# wiring1.net
KiCad netlist of a schematic drawn in EAGLE
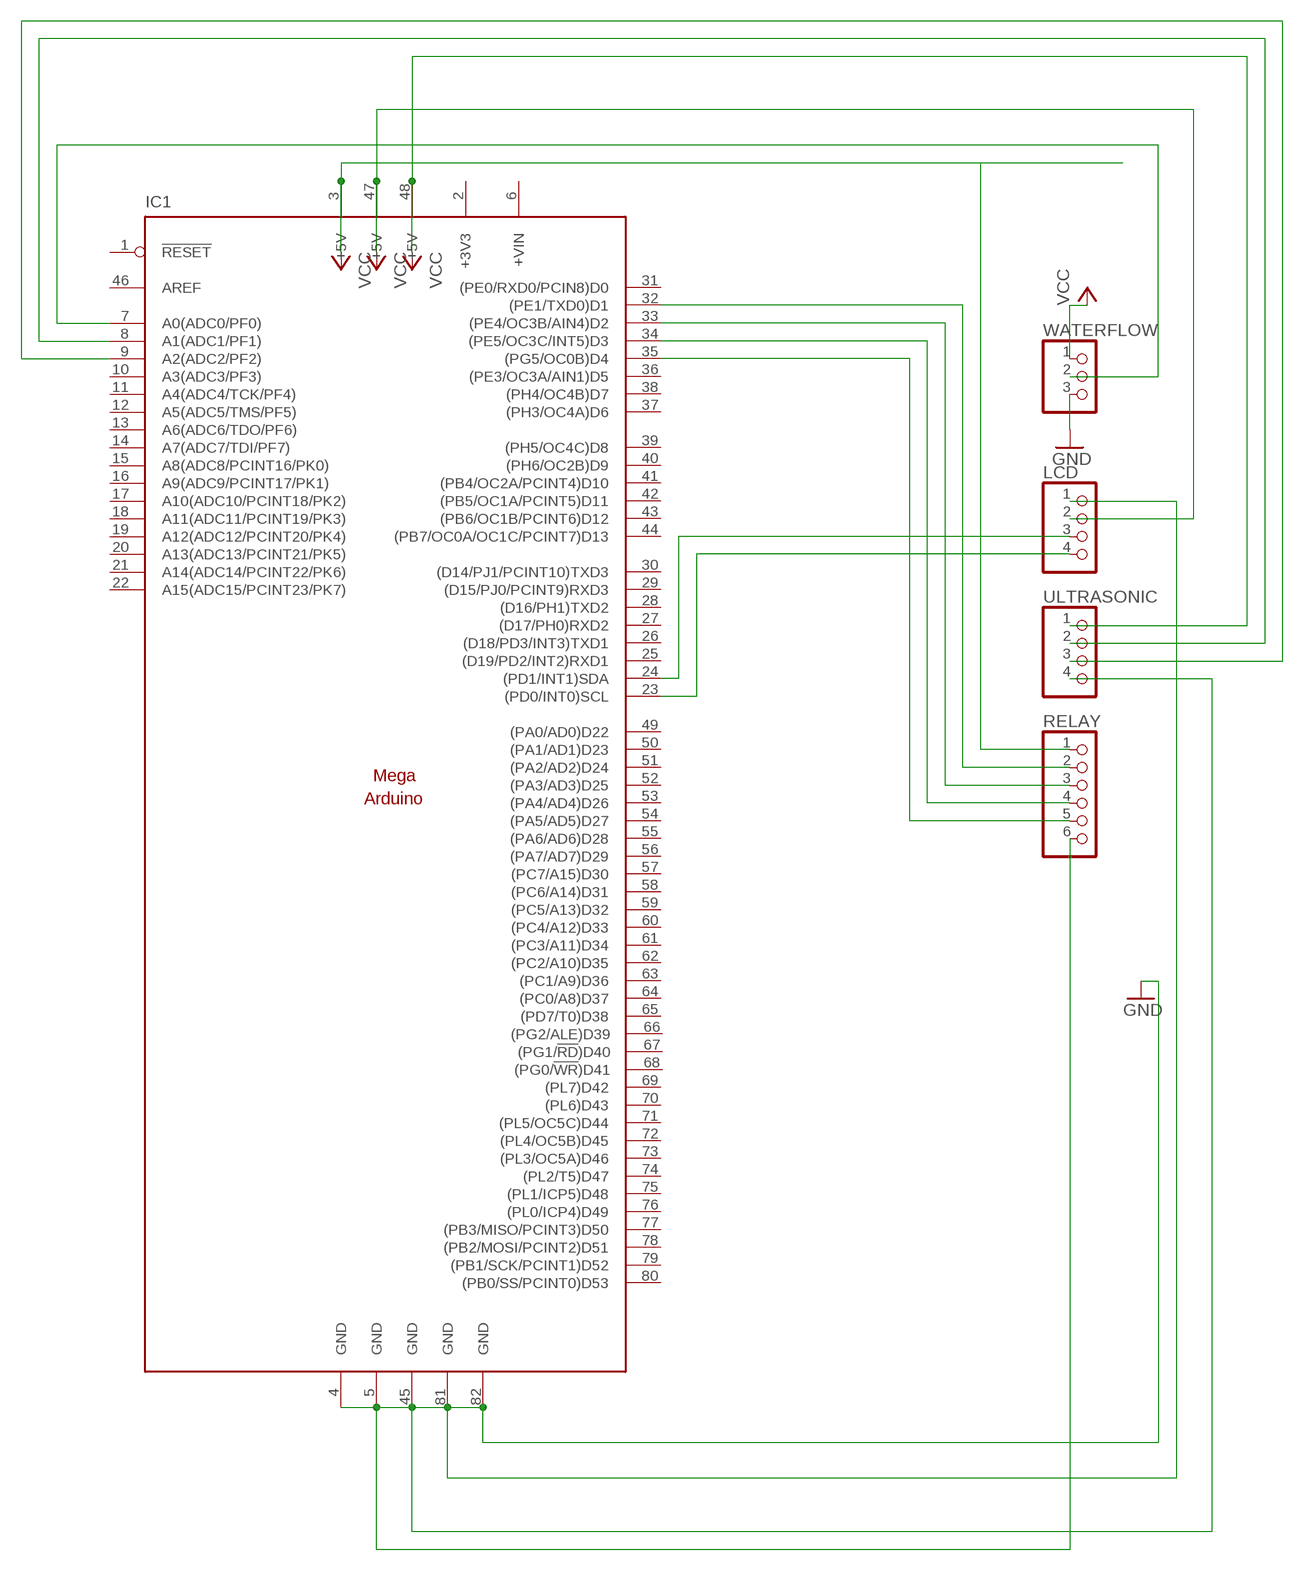
[diagram p0: schematic, sheet 1]

(export (version "E")
  (design (tool "Eeschema 10.0.6"))
  (components
    (comp (ref "IC1")
      (value "ARDUINOMEGA")
      (footprint "eagle-import:ARDUINOMEGA")
      (libsource (lib "eagle-import") (part "ARDUINOMEGA"))
    )
    (comp (ref "LCD")
      (value "PINHD-1X4")
      (footprint "eagle-import:1X04")
      (libsource (lib "eagle-import") (part "PINHD-1X4"))
    )
    (comp (ref "RELAY")
      (value "PINHD-1X6")
      (footprint "eagle-import:1X06")
      (libsource (lib "eagle-import") (part "PINHD-1X6"))
    )
    (comp (ref "ULTRASONIC")
      (value "PINHD-1X4")
      (footprint "eagle-import:1X04")
      (libsource (lib "eagle-import") (part "PINHD-1X4"))
    )
    (comp (ref "WATERFLOW")
      (value "PINHD-1X3")
      (footprint "eagle-import:1X03")
      (libsource (lib "eagle-import") (part "PINHD-1X3"))
    )
  )
  (nets
    (net (code "1") (name "/+3V3") (class "Default")
      (node (ref "IC1") (pin "2") (pinfunction "+3V3_2") (pintype "power_in"))
    )
    (net (code "2") (name "/+VIN") (class "Default")
      (node (ref "IC1") (pin "6") (pinfunction "+VIN_6") (pintype "power_in"))
    )
    (net (code "3") (name "GND") (class "Default")
      (node (ref "IC1") (pin "4") (pinfunction "GND_4") (pintype "power_in"))
      (node (ref "IC1") (pin "45") (pinfunction "GND_45") (pintype "power_in"))
      (node (ref "IC1") (pin "5") (pinfunction "GND_5") (pintype "power_in"))
      (node (ref "IC1") (pin "81") (pinfunction "GND_81") (pintype "power_in"))
      (node (ref "IC1") (pin "82") (pinfunction "GND_82") (pintype "power_in"))
      (node (ref "LCD") (pin "1") (pinfunction "1_1") (pintype "passive"))
      (node (ref "RELAY") (pin "6") (pinfunction "6_6") (pintype "passive"))
      (node (ref "ULTRASONIC") (pin "4") (pinfunction "4_4") (pintype "passive"))
      (node (ref "WATERFLOW") (pin "3") (pinfunction "3_3") (pintype "passive"))
    )
    (net (code "4") (name "Net-(IC1-(PD0{slash}INT0)SCL)") (class "Default")
      (node (ref "IC1") (pin "23") (pinfunction "(PD0/INT0)SCL_23") (pintype "bidirectional"))
      (node (ref "LCD") (pin "4") (pinfunction "4_4") (pintype "passive"))
    )
    (net (code "5") (name "Net-(IC1-(PD1{slash}INT1)SDA)") (class "Default")
      (node (ref "IC1") (pin "24") (pinfunction "(PD1/INT1)SDA_24") (pintype "bidirectional"))
      (node (ref "LCD") (pin "3") (pinfunction "3_3") (pintype "passive"))
    )
    (net (code "6") (name "Net-(IC1-(PE1{slash}TXD0)D1)") (class "Default")
      (node (ref "IC1") (pin "32") (pinfunction "(PE1/TXD0)D1_32") (pintype "bidirectional"))
      (node (ref "RELAY") (pin "2") (pinfunction "2_2") (pintype "passive"))
    )
    (net (code "7") (name "Net-(IC1-(PE4{slash}OC3B{slash}AIN4)D2)") (class "Default")
      (node (ref "IC1") (pin "33") (pinfunction "(PE4/OC3B/AIN4)D2_33") (pintype "bidirectional"))
      (node (ref "RELAY") (pin "3") (pinfunction "3_3") (pintype "passive"))
    )
    (net (code "8") (name "Net-(IC1-(PE5{slash}OC3C{slash}INT5)D3)") (class "Default")
      (node (ref "IC1") (pin "34") (pinfunction "(PE5/OC3C/INT5)D3_34") (pintype "bidirectional"))
      (node (ref "RELAY") (pin "4") (pinfunction "4_4") (pintype "passive"))
    )
    (net (code "9") (name "Net-(IC1-(PG5{slash}OC0B)D4)") (class "Default")
      (node (ref "IC1") (pin "35") (pinfunction "(PG5/OC0B)D4_35") (pintype "bidirectional"))
      (node (ref "RELAY") (pin "5") (pinfunction "5_5") (pintype "passive"))
    )
    (net (code "10") (name "Net-(IC1-A0(ADC0{slash}PF0))") (class "Default")
      (node (ref "IC1") (pin "7") (pinfunction "A0(ADC0/PF0)_7") (pintype "bidirectional"))
      (node (ref "WATERFLOW") (pin "2") (pinfunction "2_2") (pintype "passive"))
    )
    (net (code "11") (name "Net-(IC1-A1(ADC1{slash}PF1))") (class "Default")
      (node (ref "IC1") (pin "8") (pinfunction "A1(ADC1/PF1)_8") (pintype "bidirectional"))
      (node (ref "ULTRASONIC") (pin "2") (pinfunction "2_2") (pintype "passive"))
    )
    (net (code "12") (name "Net-(IC1-A2(ADC2{slash}PF2))") (class "Default")
      (node (ref "IC1") (pin "9") (pinfunction "A2(ADC2/PF2)_9") (pintype "bidirectional"))
      (node (ref "ULTRASONIC") (pin "3") (pinfunction "3_3") (pintype "passive"))
    )
    (net (code "13") (name "VCC") (class "Default")
      (node (ref "IC1") (pin "3") (pinfunction "+5V_3") (pintype "power_in"))
      (node (ref "IC1") (pin "47") (pinfunction "+5V_47") (pintype "power_in"))
      (node (ref "IC1") (pin "48") (pinfunction "+5V_48") (pintype "power_in"))
      (node (ref "LCD") (pin "2") (pinfunction "2_2") (pintype "passive"))
      (node (ref "RELAY") (pin "1") (pinfunction "1_1") (pintype "passive"))
      (node (ref "ULTRASONIC") (pin "1") (pinfunction "1_1") (pintype "passive"))
      (node (ref "WATERFLOW") (pin "1") (pinfunction "1_1") (pintype "passive"))
    )
    (net (code "14") (name "unconnected-(IC1-(D14{slash}PJ1{slash}PCINT10)TXD3-Pad30)") (class "Default")
      (node (ref "IC1") (pin "30") (pinfunction "(D14/PJ1/PCINT10)TXD3_30") (pintype "bidirectional"))
    )
    (net (code "15") (name "unconnected-(IC1-(D15{slash}PJ0{slash}PCINT9)RXD3-Pad29)") (class "Default")
      (node (ref "IC1") (pin "29") (pinfunction "(D15/PJ0/PCINT9)RXD3_29") (pintype "bidirectional"))
    )
    (net (code "16") (name "unconnected-(IC1-(D16{slash}PH1)TXD2-Pad28)") (class "Default")
      (node (ref "IC1") (pin "28") (pinfunction "(D16/PH1)TXD2_28") (pintype "bidirectional"))
    )
    (net (code "17") (name "unconnected-(IC1-(D17{slash}PH0)RXD2-Pad27)") (class "Default")
      (node (ref "IC1") (pin "27") (pinfunction "(D17/PH0)RXD2_27") (pintype "bidirectional"))
    )
    (net (code "18") (name "unconnected-(IC1-(D18{slash}PD3{slash}INT3)TXD1-Pad26)") (class "Default")
      (node (ref "IC1") (pin "26") (pinfunction "(D18/PD3/INT3)TXD1_26") (pintype "bidirectional"))
    )
    (net (code "19") (name "unconnected-(IC1-(D19{slash}PD2{slash}INT2)RXD1-Pad25)") (class "Default")
      (node (ref "IC1") (pin "25") (pinfunction "(D19/PD2/INT2)RXD1_25") (pintype "bidirectional"))
    )
    (net (code "20") (name "unconnected-(IC1-(PA0{slash}AD0)D22-Pad49)") (class "Default")
      (node (ref "IC1") (pin "49") (pinfunction "(PA0/AD0)D22_49") (pintype "bidirectional"))
    )
    (net (code "21") (name "unconnected-(IC1-(PA1{slash}AD1)D23-Pad50)") (class "Default")
      (node (ref "IC1") (pin "50") (pinfunction "(PA1/AD1)D23_50") (pintype "bidirectional"))
    )
    (net (code "22") (name "unconnected-(IC1-(PA2{slash}AD2)D24-Pad51)") (class "Default")
      (node (ref "IC1") (pin "51") (pinfunction "(PA2/AD2)D24_51") (pintype "bidirectional"))
    )
    (net (code "23") (name "unconnected-(IC1-(PA3{slash}AD3)D25-Pad52)") (class "Default")
      (node (ref "IC1") (pin "52") (pinfunction "(PA3/AD3)D25_52") (pintype "bidirectional"))
    )
    (net (code "24") (name "unconnected-(IC1-(PA4{slash}AD4)D26-Pad53)") (class "Default")
      (node (ref "IC1") (pin "53") (pinfunction "(PA4/AD4)D26_53") (pintype "bidirectional"))
    )
    (net (code "25") (name "unconnected-(IC1-(PA5{slash}AD5)D27-Pad54)") (class "Default")
      (node (ref "IC1") (pin "54") (pinfunction "(PA5/AD5)D27_54") (pintype "bidirectional"))
    )
    (net (code "26") (name "unconnected-(IC1-(PA6{slash}AD6)D28-Pad55)") (class "Default")
      (node (ref "IC1") (pin "55") (pinfunction "(PA6/AD6)D28_55") (pintype "bidirectional"))
    )
    (net (code "27") (name "unconnected-(IC1-(PA7{slash}AD7)D29-Pad56)") (class "Default")
      (node (ref "IC1") (pin "56") (pinfunction "(PA7/AD7)D29_56") (pintype "bidirectional"))
    )
    (net (code "28") (name "unconnected-(IC1-(PB0{slash}SS{slash}PCINT0)D53-Pad80)") (class "Default")
      (node (ref "IC1") (pin "80") (pinfunction "(PB0/SS/PCINT0)D53_80") (pintype "bidirectional"))
    )
    (net (code "29") (name "unconnected-(IC1-(PB1{slash}SCK{slash}PCINT1)D52-Pad79)") (class "Default")
      (node (ref "IC1") (pin "79") (pinfunction "(PB1/SCK/PCINT1)D52_79") (pintype "bidirectional"))
    )
    (net (code "30") (name "unconnected-(IC1-(PB2{slash}MOSI{slash}PCINT2)D51-Pad78)") (class "Default")
      (node (ref "IC1") (pin "78") (pinfunction "(PB2/MOSI/PCINT2)D51_78") (pintype "bidirectional"))
    )
    (net (code "31") (name "unconnected-(IC1-(PB3{slash}MISO{slash}PCINT3)D50-Pad77)") (class "Default")
      (node (ref "IC1") (pin "77") (pinfunction "(PB3/MISO/PCINT3)D50_77") (pintype "bidirectional"))
    )
    (net (code "32") (name "unconnected-(IC1-(PB4{slash}OC2A{slash}PCINT4)D10-Pad41)") (class "Default")
      (node (ref "IC1") (pin "41") (pinfunction "(PB4/OC2A/PCINT4)D10_41") (pintype "bidirectional"))
    )
    (net (code "33") (name "unconnected-(IC1-(PB5{slash}OC1A{slash}PCINT5)D11-Pad42)") (class "Default")
      (node (ref "IC1") (pin "42") (pinfunction "(PB5/OC1A/PCINT5)D11_42") (pintype "bidirectional"))
    )
    (net (code "34") (name "unconnected-(IC1-(PB6{slash}OC1B{slash}PCINT6)D12-Pad43)") (class "Default")
      (node (ref "IC1") (pin "43") (pinfunction "(PB6/OC1B/PCINT6)D12_43") (pintype "bidirectional"))
    )
    (net (code "35") (name "unconnected-(IC1-(PB7{slash}OC0A{slash}OC1C{slash}PCINT7)D13-Pad44)") (class "Default")
      (node (ref "IC1") (pin "44") (pinfunction "(PB7/OC0A/OC1C/PCINT7)D13_44") (pintype "bidirectional"))
    )
    (net (code "36") (name "unconnected-(IC1-(PC0{slash}A8)D37-Pad64)") (class "Default")
      (node (ref "IC1") (pin "64") (pinfunction "(PC0/A8)D37_64") (pintype "bidirectional"))
    )
    (net (code "37") (name "unconnected-(IC1-(PC1{slash}A9)D36-Pad63)") (class "Default")
      (node (ref "IC1") (pin "63") (pinfunction "(PC1/A9)D36_63") (pintype "bidirectional"))
    )
    (net (code "38") (name "unconnected-(IC1-(PC2{slash}A10)D35-Pad62)") (class "Default")
      (node (ref "IC1") (pin "62") (pinfunction "(PC2/A10)D35_62") (pintype "bidirectional"))
    )
    (net (code "39") (name "unconnected-(IC1-(PC3{slash}A11)D34-Pad61)") (class "Default")
      (node (ref "IC1") (pin "61") (pinfunction "(PC3/A11)D34_61") (pintype "bidirectional"))
    )
    (net (code "40") (name "unconnected-(IC1-(PC4{slash}A12)D33-Pad60)") (class "Default")
      (node (ref "IC1") (pin "60") (pinfunction "(PC4/A12)D33_60") (pintype "bidirectional"))
    )
    (net (code "41") (name "unconnected-(IC1-(PC5{slash}A13)D32-Pad59)") (class "Default")
      (node (ref "IC1") (pin "59") (pinfunction "(PC5/A13)D32_59") (pintype "bidirectional"))
    )
    (net (code "42") (name "unconnected-(IC1-(PC6{slash}A14)D31-Pad58)") (class "Default")
      (node (ref "IC1") (pin "58") (pinfunction "(PC6/A14)D31_58") (pintype "bidirectional"))
    )
    (net (code "43") (name "unconnected-(IC1-(PC7{slash}A15)D30-Pad57)") (class "Default")
      (node (ref "IC1") (pin "57") (pinfunction "(PC7/A15)D30_57") (pintype "bidirectional"))
    )
    (net (code "44") (name "unconnected-(IC1-(PD7{slash}T0)D38-Pad65)") (class "Default")
      (node (ref "IC1") (pin "65") (pinfunction "(PD7/T0)D38_65") (pintype "bidirectional"))
    )
    (net (code "45") (name "unconnected-(IC1-(PE0{slash}RXD0{slash}PCIN8)D0-Pad31)") (class "Default")
      (node (ref "IC1") (pin "31") (pinfunction "(PE0/RXD0/PCIN8)D0_31") (pintype "bidirectional"))
    )
    (net (code "46") (name "unconnected-(IC1-(PE3{slash}OC3A{slash}AIN1)D5-Pad36)") (class "Default")
      (node (ref "IC1") (pin "36") (pinfunction "(PE3/OC3A/AIN1)D5_36") (pintype "bidirectional"))
    )
    (net (code "47") (name "unconnected-(IC1-(PG0{slash}~{WR})D41-Pad68)") (class "Default")
      (node (ref "IC1") (pin "68") (pinfunction "(PG0/~{WR})D41_68") (pintype "bidirectional"))
    )
    (net (code "48") (name "unconnected-(IC1-(PG1{slash}~{RD})D40-Pad67)") (class "Default")
      (node (ref "IC1") (pin "67") (pinfunction "(PG1/~{RD})D40_67") (pintype "bidirectional"))
    )
    (net (code "49") (name "unconnected-(IC1-(PG2{slash}ALE)D39-Pad66)") (class "Default")
      (node (ref "IC1") (pin "66") (pinfunction "(PG2/ALE)D39_66") (pintype "bidirectional"))
    )
    (net (code "50") (name "unconnected-(IC1-(PH3{slash}OC4A)D6-Pad37)") (class "Default")
      (node (ref "IC1") (pin "37") (pinfunction "(PH3/OC4A)D6_37") (pintype "bidirectional"))
    )
    (net (code "51") (name "unconnected-(IC1-(PH4{slash}OC4B)D7-Pad38)") (class "Default")
      (node (ref "IC1") (pin "38") (pinfunction "(PH4/OC4B)D7_38") (pintype "bidirectional"))
    )
    (net (code "52") (name "unconnected-(IC1-(PH5{slash}OC4C)D8-Pad39)") (class "Default")
      (node (ref "IC1") (pin "39") (pinfunction "(PH5/OC4C)D8_39") (pintype "bidirectional"))
    )
    (net (code "53") (name "unconnected-(IC1-(PH6{slash}OC2B)D9-Pad40)") (class "Default")
      (node (ref "IC1") (pin "40") (pinfunction "(PH6/OC2B)D9_40") (pintype "bidirectional"))
    )
    (net (code "54") (name "unconnected-(IC1-(PL0{slash}ICP4)D49-Pad76)") (class "Default")
      (node (ref "IC1") (pin "76") (pinfunction "(PL0/ICP4)D49_76") (pintype "bidirectional"))
    )
    (net (code "55") (name "unconnected-(IC1-(PL1{slash}ICP5)D48-Pad75)") (class "Default")
      (node (ref "IC1") (pin "75") (pinfunction "(PL1/ICP5)D48_75") (pintype "bidirectional"))
    )
    (net (code "56") (name "unconnected-(IC1-(PL2{slash}T5)D47-Pad74)") (class "Default")
      (node (ref "IC1") (pin "74") (pinfunction "(PL2/T5)D47_74") (pintype "bidirectional"))
    )
    (net (code "57") (name "unconnected-(IC1-(PL3{slash}OC5A)D46-Pad73)") (class "Default")
      (node (ref "IC1") (pin "73") (pinfunction "(PL3/OC5A)D46_73") (pintype "bidirectional"))
    )
    (net (code "58") (name "unconnected-(IC1-(PL4{slash}OC5B)D45-Pad72)") (class "Default")
      (node (ref "IC1") (pin "72") (pinfunction "(PL4/OC5B)D45_72") (pintype "bidirectional"))
    )
    (net (code "59") (name "unconnected-(IC1-(PL5{slash}OC5C)D44-Pad71)") (class "Default")
      (node (ref "IC1") (pin "71") (pinfunction "(PL5/OC5C)D44_71") (pintype "bidirectional"))
    )
    (net (code "60") (name "unconnected-(IC1-(PL6)D43-Pad70)") (class "Default")
      (node (ref "IC1") (pin "70") (pinfunction "(PL6)D43_70") (pintype "bidirectional"))
    )
    (net (code "61") (name "unconnected-(IC1-(PL7)D42-Pad69)") (class "Default")
      (node (ref "IC1") (pin "69") (pinfunction "(PL7)D42_69") (pintype "bidirectional"))
    )
    (net (code "62") (name "unconnected-(IC1-A3(ADC3{slash}PF3)-Pad10)") (class "Default")
      (node (ref "IC1") (pin "10") (pinfunction "A3(ADC3/PF3)_10") (pintype "bidirectional"))
    )
    (net (code "63") (name "unconnected-(IC1-A4(ADC4{slash}TCK{slash}PF4)-Pad11)") (class "Default")
      (node (ref "IC1") (pin "11") (pinfunction "A4(ADC4/TCK/PF4)_11") (pintype "bidirectional"))
    )
    (net (code "64") (name "unconnected-(IC1-A5(ADC5{slash}TMS{slash}PF5)-Pad12)") (class "Default")
      (node (ref "IC1") (pin "12") (pinfunction "A5(ADC5/TMS/PF5)_12") (pintype "bidirectional"))
    )
    (net (code "65") (name "unconnected-(IC1-A6(ADC6{slash}TDO{slash}PF6)-Pad13)") (class "Default")
      (node (ref "IC1") (pin "13") (pinfunction "A6(ADC6/TDO/PF6)_13") (pintype "bidirectional"))
    )
    (net (code "66") (name "unconnected-(IC1-A7(ADC7{slash}TDI{slash}PF7)-Pad14)") (class "Default")
      (node (ref "IC1") (pin "14") (pinfunction "A7(ADC7/TDI/PF7)_14") (pintype "bidirectional"))
    )
    (net (code "67") (name "unconnected-(IC1-A8(ADC8{slash}PCINT16{slash}PK0)-Pad15)") (class "Default")
      (node (ref "IC1") (pin "15") (pinfunction "A8(ADC8/PCINT16/PK0)_15") (pintype "bidirectional"))
    )
    (net (code "68") (name "unconnected-(IC1-A9(ADC9{slash}PCINT17{slash}PK1)-Pad16)") (class "Default")
      (node (ref "IC1") (pin "16") (pinfunction "A9(ADC9/PCINT17/PK1)_16") (pintype "bidirectional"))
    )
    (net (code "69") (name "unconnected-(IC1-A10(ADC10{slash}PCINT18{slash}PK2)-Pad17)") (class "Default")
      (node (ref "IC1") (pin "17") (pinfunction "A10(ADC10/PCINT18/PK2)_17") (pintype "bidirectional"))
    )
    (net (code "70") (name "unconnected-(IC1-A11(ADC11{slash}PCINT19{slash}PK3)-Pad18)") (class "Default")
      (node (ref "IC1") (pin "18") (pinfunction "A11(ADC11/PCINT19/PK3)_18") (pintype "bidirectional"))
    )
    (net (code "71") (name "unconnected-(IC1-A12(ADC12{slash}PCINT20{slash}PK4)-Pad19)") (class "Default")
      (node (ref "IC1") (pin "19") (pinfunction "A12(ADC12/PCINT20/PK4)_19") (pintype "bidirectional"))
    )
    (net (code "72") (name "unconnected-(IC1-A13(ADC13{slash}PCINT21{slash}PK5)-Pad20)") (class "Default")
      (node (ref "IC1") (pin "20") (pinfunction "A13(ADC13/PCINT21/PK5)_20") (pintype "bidirectional"))
    )
    (net (code "73") (name "unconnected-(IC1-A14(ADC14{slash}PCINT22{slash}PK6)-Pad21)") (class "Default")
      (node (ref "IC1") (pin "21") (pinfunction "A14(ADC14/PCINT22/PK6)_21") (pintype "bidirectional"))
    )
    (net (code "74") (name "unconnected-(IC1-A15(ADC15{slash}PCINT23{slash}PK7)-Pad22)") (class "Default")
      (node (ref "IC1") (pin "22") (pinfunction "A15(ADC15/PCINT23/PK7)_22") (pintype "bidirectional"))
    )
    (net (code "75") (name "unconnected-(IC1-AREF-Pad46)") (class "Default")
      (node (ref "IC1") (pin "46") (pinfunction "AREF_46") (pintype "bidirectional"))
    )
    (net (code "76") (name "unconnected-(IC1-~{RESET}-Pad1)") (class "Default")
      (node (ref "IC1") (pin "1") (pinfunction "~{RESET}_1") (pintype "bidirectional"))
    )
  )
)
